# untitled.net
KiCad netlist of a schematic drawn in EAGLE
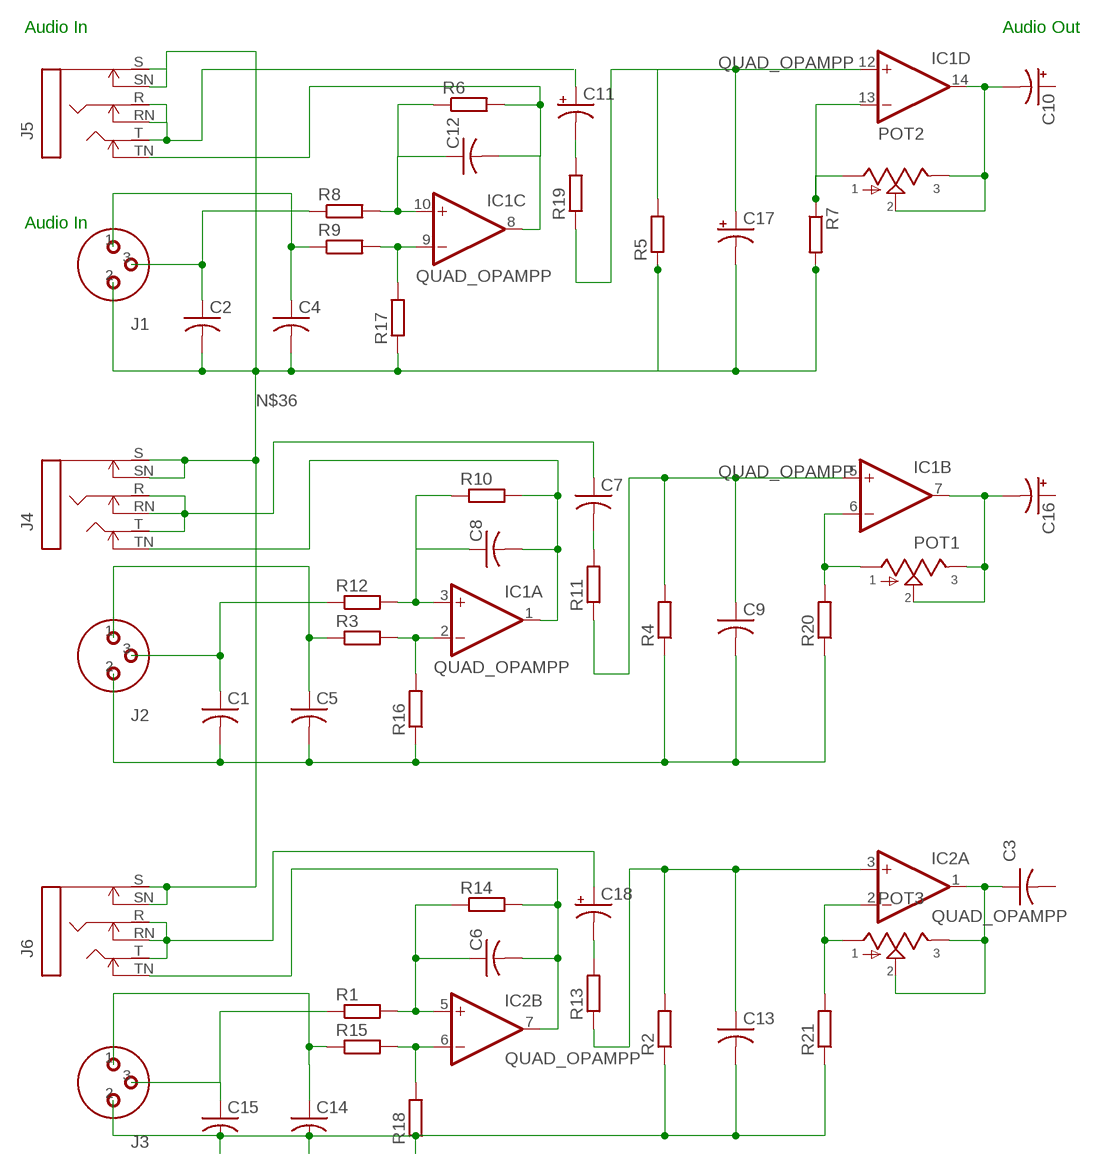
[diagram p0: schematic, sheet 1]

(export (version "E")
  (design (tool "Eeschema 10.0.6"))
  (components
    (comp (ref "C1")
      (value "C-US025-030X050")
      (footprint "eagle-import:C025-030X050")
      (libsource (lib "eagle-import") (part "C-US025-030X050"))
    )
    (comp (ref "C2")
      (value "C-US025-030X050")
      (footprint "eagle-import:C025-030X050")
      (libsource (lib "eagle-import") (part "C-US025-030X050"))
    )
    (comp (ref "C3")
      (value "C-US025-030X050")
      (footprint "eagle-import:C025-030X050")
      (libsource (lib "eagle-import") (part "C-US025-030X050"))
    )
    (comp (ref "C4")
      (value "C-US025-030X050")
      (footprint "eagle-import:C025-030X050")
      (libsource (lib "eagle-import") (part "C-US025-030X050"))
    )
    (comp (ref "C5")
      (value "C-US025-030X050")
      (footprint "eagle-import:C025-030X050")
      (libsource (lib "eagle-import") (part "C-US025-030X050"))
    )
    (comp (ref "C6")
      (value "C-US025-030X050")
      (footprint "eagle-import:C025-030X050")
      (libsource (lib "eagle-import") (part "C-US025-030X050"))
    )
    (comp (ref "C7")
      (value "C-US025-030X050")
      (footprint "eagle-import:C025-030X050")
      (libsource (lib "eagle-import") (part "C-US025-030X050"))
    )
    (comp (ref "C8")
      (value "C-US025-030X050")
      (footprint "eagle-import:C025-030X050")
      (libsource (lib "eagle-import") (part "C-US025-030X050"))
    )
    (comp (ref "C9")
      (value "C-US025-030X050")
      (footprint "eagle-import:C025-030X050")
      (libsource (lib "eagle-import") (part "C-US025-030X050"))
    )
    (comp (ref "C10")
      (value "CPOL-USE1.8-4")
      (footprint "eagle-import:E1,8-4")
      (libsource (lib "eagle-import") (part "CPOL-USE1.8-4"))
    )
    (comp (ref "C11")
      (value "CPOL-USE1.8-4")
      (footprint "eagle-import:E1,8-4")
      (libsource (lib "eagle-import") (part "CPOL-USE1.8-4"))
    )
    (comp (ref "C12")
      (value "C-US025-030X050")
      (footprint "eagle-import:C025-030X050")
      (libsource (lib "eagle-import") (part "C-US025-030X050"))
    )
    (comp (ref "C13")
      (value "C-US025-030X050")
      (footprint "eagle-import:C025-030X050")
      (libsource (lib "eagle-import") (part "C-US025-030X050"))
    )
    (comp (ref "C14")
      (value "C-US025-030X050")
      (footprint "eagle-import:C025-030X050")
      (libsource (lib "eagle-import") (part "C-US025-030X050"))
    )
    (comp (ref "C15")
      (value "C-US025-030X050")
      (footprint "eagle-import:C025-030X050")
      (libsource (lib "eagle-import") (part "C-US025-030X050"))
    )
    (comp (ref "C16")
      (value "CPOL-USE1.8-4")
      (footprint "eagle-import:E1,8-4")
      (libsource (lib "eagle-import") (part "CPOL-USE1.8-4"))
    )
    (comp (ref "C17")
      (value "CPOL-USE1.8-4")
      (footprint "eagle-import:E1,8-4")
      (libsource (lib "eagle-import") (part "CPOL-USE1.8-4"))
    )
    (comp (ref "C18")
      (value "CPOL-USE1.8-4")
      (footprint "eagle-import:E1,8-4")
      (libsource (lib "eagle-import") (part "CPOL-USE1.8-4"))
    )
    (comp (ref "IC1")
      (value "QUAD_OPAMPP")
      (footprint "eagle-import:DIL14")
      (libsource (lib "eagle-import") (part "QUAD_OPAMPP"))
    )
    (comp (ref "IC2")
      (value "QUAD_OPAMPP")
      (footprint "eagle-import:DIL14")
      (libsource (lib "eagle-import") (part "QUAD_OPAMPP"))
    )
    (comp (ref "J1")
      (value "XLR")
      (footprint "eagle-import:XLR_PADS")
      (libsource (lib "eagle-import") (part "XLR"))
    )
    (comp (ref "J2")
      (value "XLR")
      (footprint "eagle-import:XLR_PADS")
      (libsource (lib "eagle-import") (part "XLR"))
    )
    (comp (ref "J3")
      (value "XLR")
      (footprint "eagle-import:XLR_PADS")
      (libsource (lib "eagle-import") (part "XLR"))
    )
    (comp (ref "J4")
      (value "STEREOSWS")
      (footprint "eagle-import:NMJ6HC-S")
      (libsource (lib "eagle-import") (part "STEREOSWS"))
    )
    (comp (ref "J5")
      (value "STEREOSWS")
      (footprint "eagle-import:NMJ6HC-S")
      (libsource (lib "eagle-import") (part "STEREOSWS"))
    )
    (comp (ref "J6")
      (value "STEREOSWS")
      (footprint "eagle-import:NMJ6HC-S")
      (libsource (lib "eagle-import") (part "STEREOSWS"))
    )
    (comp (ref "POT1")
      (value "POT")
      (footprint "eagle-import:POT")
      (libsource (lib "eagle-import") (part "POT"))
    )
    (comp (ref "POT2")
      (value "POT")
      (footprint "eagle-import:POT")
      (libsource (lib "eagle-import") (part "POT"))
    )
    (comp (ref "POT3")
      (value "POT")
      (footprint "eagle-import:POT")
      (libsource (lib "eagle-import") (part "POT"))
    )
    (comp (ref "R1")
      (value "R-EU_0204/7")
      (footprint "eagle-import:0204_7")
      (libsource (lib "eagle-import") (part "R-EU_0204/7"))
    )
    (comp (ref "R2")
      (value "R-EU_0204/7")
      (footprint "eagle-import:0204_7")
      (libsource (lib "eagle-import") (part "R-EU_0204/7"))
    )
    (comp (ref "R3")
      (value "R-EU_0204/7")
      (footprint "eagle-import:0204_7")
      (libsource (lib "eagle-import") (part "R-EU_0204/7"))
    )
    (comp (ref "R4")
      (value "R-EU_0204/7")
      (footprint "eagle-import:0204_7")
      (libsource (lib "eagle-import") (part "R-EU_0204/7"))
    )
    (comp (ref "R5")
      (value "R-EU_0204/7")
      (footprint "eagle-import:0204_7")
      (libsource (lib "eagle-import") (part "R-EU_0204/7"))
    )
    (comp (ref "R6")
      (value "R-EU_0204/7")
      (footprint "eagle-import:0204_7")
      (libsource (lib "eagle-import") (part "R-EU_0204/7"))
    )
    (comp (ref "R7")
      (value "R-EU_0204/7")
      (footprint "eagle-import:0204_7")
      (libsource (lib "eagle-import") (part "R-EU_0204/7"))
    )
    (comp (ref "R8")
      (value "R-EU_0204/7")
      (footprint "eagle-import:0204_7")
      (libsource (lib "eagle-import") (part "R-EU_0204/7"))
    )
    (comp (ref "R9")
      (value "R-EU_0204/7")
      (footprint "eagle-import:0204_7")
      (libsource (lib "eagle-import") (part "R-EU_0204/7"))
    )
    (comp (ref "R10")
      (value "R-EU_0204/7")
      (footprint "eagle-import:0204_7")
      (libsource (lib "eagle-import") (part "R-EU_0204/7"))
    )
    (comp (ref "R11")
      (value "R-EU_0204/7")
      (footprint "eagle-import:0204_7")
      (libsource (lib "eagle-import") (part "R-EU_0204/7"))
    )
    (comp (ref "R12")
      (value "R-EU_0204/7")
      (footprint "eagle-import:0204_7")
      (libsource (lib "eagle-import") (part "R-EU_0204/7"))
    )
    (comp (ref "R13")
      (value "R-EU_0204/7")
      (footprint "eagle-import:0204_7")
      (libsource (lib "eagle-import") (part "R-EU_0204/7"))
    )
    (comp (ref "R14")
      (value "R-EU_0204/7")
      (footprint "eagle-import:0204_7")
      (libsource (lib "eagle-import") (part "R-EU_0204/7"))
    )
    (comp (ref "R15")
      (value "R-EU_0204/7")
      (footprint "eagle-import:0204_7")
      (libsource (lib "eagle-import") (part "R-EU_0204/7"))
    )
    (comp (ref "R16")
      (value "R-EU_0204/7")
      (footprint "eagle-import:0204_7")
      (libsource (lib "eagle-import") (part "R-EU_0204/7"))
    )
    (comp (ref "R17")
      (value "R-EU_0204/7")
      (footprint "eagle-import:0204_7")
      (libsource (lib "eagle-import") (part "R-EU_0204/7"))
    )
    (comp (ref "R18")
      (value "R-EU_0204/7")
      (footprint "eagle-import:0204_7")
      (libsource (lib "eagle-import") (part "R-EU_0204/7"))
    )
    (comp (ref "R19")
      (value "R-EU_0204/7")
      (footprint "eagle-import:0204_7")
      (libsource (lib "eagle-import") (part "R-EU_0204/7"))
    )
    (comp (ref "R20")
      (value "R-EU_0204/7")
      (footprint "eagle-import:0204_7")
      (libsource (lib "eagle-import") (part "R-EU_0204/7"))
    )
    (comp (ref "R21")
      (value "R-EU_0204/7")
      (footprint "eagle-import:0204_7")
      (libsource (lib "eagle-import") (part "R-EU_0204/7"))
    )
  )
  (nets
    (net (code "1") (name "/N$36") (class "Default")
      (node (ref "C17") (pin "-") (pinfunction "-_-") (pintype "passive"))
      (node (ref "C2") (pin "2") (pinfunction "2_2") (pintype "passive"))
      (node (ref "C4") (pin "2") (pinfunction "2_2") (pintype "passive"))
      (node (ref "J1") (pin "2") (pinfunction "2_2") (pintype "passive"))
      (node (ref "J4") (pin "S") (pinfunction "S_S") (pintype "passive"))
      (node (ref "J4") (pin "SN") (pinfunction "SN_SN") (pintype "passive"))
      (node (ref "J5") (pin "S") (pinfunction "S_S") (pintype "passive"))
      (node (ref "J5") (pin "SN") (pinfunction "SN_SN") (pintype "passive"))
      (node (ref "J6") (pin "S") (pinfunction "S_S") (pintype "passive"))
      (node (ref "J6") (pin "SN") (pinfunction "SN_SN") (pintype "passive"))
      (node (ref "R17") (pin "1") (pinfunction "1_1") (pintype "passive"))
      (node (ref "R5") (pin "1") (pinfunction "1_1") (pintype "passive"))
      (node (ref "R7") (pin "2") (pinfunction "2_2") (pintype "passive"))
    )
    (net (code "2") (name "Net-(C1-Pad1)") (class "Default")
      (node (ref "C1") (pin "1") (pinfunction "1_1") (pintype "passive"))
      (node (ref "J2") (pin "3") (pinfunction "3_3") (pintype "passive"))
      (node (ref "R12") (pin "1") (pinfunction "1_1") (pintype "passive"))
    )
    (net (code "3") (name "Net-(C1-Pad2)") (class "Default")
      (node (ref "C1") (pin "2") (pinfunction "2_2") (pintype "passive"))
      (node (ref "C5") (pin "2") (pinfunction "2_2") (pintype "passive"))
      (node (ref "C9") (pin "2") (pinfunction "2_2") (pintype "passive"))
      (node (ref "J2") (pin "2") (pinfunction "2_2") (pintype "passive"))
      (node (ref "R16") (pin "1") (pinfunction "1_1") (pintype "passive"))
      (node (ref "R20") (pin "1") (pinfunction "1_1") (pintype "passive"))
      (node (ref "R4") (pin "1") (pinfunction "1_1") (pintype "passive"))
    )
    (net (code "4") (name "Net-(C2-Pad1)") (class "Default")
      (node (ref "C2") (pin "1") (pinfunction "1_1") (pintype "passive"))
      (node (ref "J1") (pin "3") (pinfunction "3_3") (pintype "passive"))
      (node (ref "R8") (pin "1") (pinfunction "1_1") (pintype "passive"))
    )
    (net (code "5") (name "Net-(C4-Pad1)") (class "Default")
      (node (ref "C4") (pin "1") (pinfunction "1_1") (pintype "passive"))
      (node (ref "J1") (pin "1") (pinfunction "1_1") (pintype "passive"))
      (node (ref "R9") (pin "1") (pinfunction "1_1") (pintype "passive"))
    )
    (net (code "6") (name "Net-(C5-Pad1)") (class "Default")
      (node (ref "C5") (pin "1") (pinfunction "1_1") (pintype "passive"))
      (node (ref "J2") (pin "1") (pinfunction "1_1") (pintype "passive"))
      (node (ref "R3") (pin "1") (pinfunction "1_1") (pintype "passive"))
    )
    (net (code "7") (name "Net-(C7-Pad1)") (class "Default")
      (node (ref "C7") (pin "1") (pinfunction "1_1") (pintype "passive"))
      (node (ref "J4") (pin "R") (pinfunction "R_R") (pintype "passive"))
      (node (ref "J4") (pin "RN") (pinfunction "RN_RN") (pintype "passive"))
      (node (ref "J4") (pin "T") (pinfunction "T_T") (pintype "passive"))
    )
    (net (code "8") (name "Net-(C7-Pad2)") (class "Default")
      (node (ref "C7") (pin "2") (pinfunction "2_2") (pintype "passive"))
      (node (ref "R11") (pin "2") (pinfunction "2_2") (pintype "passive"))
    )
    (net (code "9") (name "Net-(C11-Pad-)") (class "Default")
      (node (ref "C11") (pin "-") (pinfunction "-_-") (pintype "passive"))
      (node (ref "R19") (pin "2") (pinfunction "2_2") (pintype "passive"))
    )
    (net (code "10") (name "Net-(C13-Pad2)") (class "Default")
      (node (ref "C13") (pin "2") (pinfunction "2_2") (pintype "passive"))
      (node (ref "C14") (pin "2") (pinfunction "2_2") (pintype "passive"))
      (node (ref "C15") (pin "2") (pinfunction "2_2") (pintype "passive"))
      (node (ref "J3") (pin "2") (pinfunction "2_2") (pintype "passive"))
      (node (ref "R18") (pin "1") (pinfunction "1_1") (pintype "passive"))
      (node (ref "R2") (pin "1") (pinfunction "1_1") (pintype "passive"))
      (node (ref "R21") (pin "1") (pinfunction "1_1") (pintype "passive"))
    )
    (net (code "11") (name "Net-(C14-Pad1)") (class "Default")
      (node (ref "C14") (pin "1") (pinfunction "1_1") (pintype "passive"))
      (node (ref "J3") (pin "1") (pinfunction "1_1") (pintype "passive"))
      (node (ref "R15") (pin "1") (pinfunction "1_1") (pintype "passive"))
    )
    (net (code "12") (name "Net-(C15-Pad1)") (class "Default")
      (node (ref "C15") (pin "1") (pinfunction "1_1") (pintype "passive"))
      (node (ref "J3") (pin "3") (pinfunction "3_3") (pintype "passive"))
      (node (ref "R1") (pin "1") (pinfunction "1_1") (pintype "passive"))
    )
    (net (code "13") (name "Net-(C18-Pad+)") (class "Default")
      (node (ref "C18") (pin "+") (pinfunction "+_+") (pintype "passive"))
      (node (ref "J6") (pin "R") (pinfunction "R_R") (pintype "passive"))
      (node (ref "J6") (pin "RN") (pinfunction "RN_RN") (pintype "passive"))
      (node (ref "J6") (pin "T") (pinfunction "T_T") (pintype "passive"))
    )
    (net (code "14") (name "Net-(C18-Pad-)") (class "Default")
      (node (ref "C18") (pin "-") (pinfunction "-_-") (pintype "passive"))
      (node (ref "R13") (pin "2") (pinfunction "2_2") (pintype "passive"))
    )
    (net (code "15") (name "Net-(IC1A-+IN)") (class "Default")
      (node (ref "C8") (pin "1") (pinfunction "1_1") (pintype "passive"))
      (node (ref "IC1") (pin "3") (pinfunction "+IN_3") (pintype "input"))
      (node (ref "R10") (pin "1") (pinfunction "1_1") (pintype "passive"))
      (node (ref "R12") (pin "2") (pinfunction "2_2") (pintype "passive"))
    )
    (net (code "16") (name "Net-(IC1A--IN)") (class "Default")
      (node (ref "IC1") (pin "2") (pinfunction "-IN_2") (pintype "input"))
      (node (ref "R16") (pin "2") (pinfunction "2_2") (pintype "passive"))
      (node (ref "R3") (pin "2") (pinfunction "2_2") (pintype "passive"))
    )
    (net (code "17") (name "Net-(IC1A-OUT)") (class "Default")
      (node (ref "C8") (pin "2") (pinfunction "2_2") (pintype "passive"))
      (node (ref "IC1") (pin "1") (pinfunction "OUT_1") (pintype "output"))
      (node (ref "J4") (pin "TN") (pinfunction "TN_TN") (pintype "passive"))
      (node (ref "R10") (pin "2") (pinfunction "2_2") (pintype "passive"))
    )
    (net (code "18") (name "Net-(IC1B-+IN)") (class "Default")
      (node (ref "C9") (pin "1") (pinfunction "1_1") (pintype "passive"))
      (node (ref "IC1") (pin "5") (pinfunction "+IN_5") (pintype "input"))
      (node (ref "R11") (pin "1") (pinfunction "1_1") (pintype "passive"))
      (node (ref "R4") (pin "2") (pinfunction "2_2") (pintype "passive"))
    )
    (net (code "19") (name "Net-(IC1B--IN)") (class "Default")
      (node (ref "IC1") (pin "6") (pinfunction "-IN_6") (pintype "input"))
      (node (ref "POT1") (pin "1") (pinfunction "1_1") (pintype "passive"))
      (node (ref "R20") (pin "2") (pinfunction "2_2") (pintype "passive"))
    )
    (net (code "20") (name "Net-(IC1B-OUT)") (class "Default")
      (node (ref "C16") (pin "-") (pinfunction "-_-") (pintype "passive"))
      (node (ref "IC1") (pin "7") (pinfunction "OUT_7") (pintype "output"))
      (node (ref "POT1") (pin "2") (pinfunction "2_2") (pintype "passive"))
      (node (ref "POT1") (pin "3") (pinfunction "3_3") (pintype "passive"))
    )
    (net (code "21") (name "Net-(IC1C-+IN)") (class "Default")
      (node (ref "C12") (pin "1") (pinfunction "1_1") (pintype "passive"))
      (node (ref "IC1") (pin "10") (pinfunction "+IN_10") (pintype "input"))
      (node (ref "R6") (pin "1") (pinfunction "1_1") (pintype "passive"))
      (node (ref "R8") (pin "2") (pinfunction "2_2") (pintype "passive"))
    )
    (net (code "22") (name "Net-(IC1C--IN)") (class "Default")
      (node (ref "IC1") (pin "9") (pinfunction "-IN_9") (pintype "input"))
      (node (ref "R17") (pin "2") (pinfunction "2_2") (pintype "passive"))
      (node (ref "R9") (pin "2") (pinfunction "2_2") (pintype "passive"))
    )
    (net (code "23") (name "Net-(IC1C-OUT)") (class "Default")
      (node (ref "C12") (pin "2") (pinfunction "2_2") (pintype "passive"))
      (node (ref "IC1") (pin "8") (pinfunction "OUT_8") (pintype "output"))
      (node (ref "J5") (pin "TN") (pinfunction "TN_TN") (pintype "passive"))
      (node (ref "R6") (pin "2") (pinfunction "2_2") (pintype "passive"))
    )
    (net (code "24") (name "Net-(IC1D-+IN)") (class "Default")
      (node (ref "C17") (pin "+") (pinfunction "+_+") (pintype "passive"))
      (node (ref "IC1") (pin "12") (pinfunction "+IN_12") (pintype "input"))
      (node (ref "R19") (pin "1") (pinfunction "1_1") (pintype "passive"))
      (node (ref "R5") (pin "2") (pinfunction "2_2") (pintype "passive"))
    )
    (net (code "25") (name "Net-(IC1D--IN)") (class "Default")
      (node (ref "IC1") (pin "13") (pinfunction "-IN_13") (pintype "input"))
      (node (ref "POT2") (pin "1") (pinfunction "1_1") (pintype "passive"))
      (node (ref "R7") (pin "1") (pinfunction "1_1") (pintype "passive"))
    )
    (net (code "26") (name "Net-(IC1D-OUT)") (class "Default")
      (node (ref "C10") (pin "-") (pinfunction "-_-") (pintype "passive"))
      (node (ref "IC1") (pin "14") (pinfunction "OUT_14") (pintype "output"))
      (node (ref "POT2") (pin "2") (pinfunction "2_2") (pintype "passive"))
      (node (ref "POT2") (pin "3") (pinfunction "3_3") (pintype "passive"))
    )
    (net (code "27") (name "Net-(IC2A-+IN)") (class "Default")
      (node (ref "C13") (pin "1") (pinfunction "1_1") (pintype "passive"))
      (node (ref "IC2") (pin "3") (pinfunction "+IN_3") (pintype "input"))
      (node (ref "R13") (pin "1") (pinfunction "1_1") (pintype "passive"))
      (node (ref "R2") (pin "2") (pinfunction "2_2") (pintype "passive"))
    )
    (net (code "28") (name "Net-(IC2A--IN)") (class "Default")
      (node (ref "IC2") (pin "2") (pinfunction "-IN_2") (pintype "input"))
      (node (ref "POT3") (pin "1") (pinfunction "1_1") (pintype "passive"))
      (node (ref "R21") (pin "2") (pinfunction "2_2") (pintype "passive"))
    )
    (net (code "29") (name "Net-(IC2A-OUT)") (class "Default")
      (node (ref "C3") (pin "1") (pinfunction "1_1") (pintype "passive"))
      (node (ref "IC2") (pin "1") (pinfunction "OUT_1") (pintype "output"))
      (node (ref "POT3") (pin "2") (pinfunction "2_2") (pintype "passive"))
      (node (ref "POT3") (pin "3") (pinfunction "3_3") (pintype "passive"))
    )
    (net (code "30") (name "Net-(IC2B-+IN)") (class "Default")
      (node (ref "C6") (pin "1") (pinfunction "1_1") (pintype "passive"))
      (node (ref "IC2") (pin "5") (pinfunction "+IN_5") (pintype "input"))
      (node (ref "R1") (pin "2") (pinfunction "2_2") (pintype "passive"))
      (node (ref "R14") (pin "1") (pinfunction "1_1") (pintype "passive"))
    )
    (net (code "31") (name "Net-(IC2B--IN)") (class "Default")
      (node (ref "IC2") (pin "6") (pinfunction "-IN_6") (pintype "input"))
      (node (ref "R15") (pin "2") (pinfunction "2_2") (pintype "passive"))
      (node (ref "R18") (pin "2") (pinfunction "2_2") (pintype "passive"))
    )
    (net (code "32") (name "Net-(IC2B-OUT)") (class "Default")
      (node (ref "C6") (pin "2") (pinfunction "2_2") (pintype "passive"))
      (node (ref "IC2") (pin "7") (pinfunction "OUT_7") (pintype "output"))
      (node (ref "J6") (pin "TN") (pinfunction "TN_TN") (pintype "passive"))
      (node (ref "R14") (pin "2") (pinfunction "2_2") (pintype "passive"))
    )
    (net (code "33") (name "Net-(J5-PadR)") (class "Default")
      (node (ref "J5") (pin "R") (pinfunction "R_R") (pintype "passive"))
      (node (ref "J5") (pin "RN") (pinfunction "RN_RN") (pintype "passive"))
      (node (ref "J5") (pin "T") (pinfunction "T_T") (pintype "passive"))
    )
    (net (code "34") (name "unconnected-(C3-Pad2)") (class "Default")
      (node (ref "C3") (pin "2") (pinfunction "2_2") (pintype "passive"))
    )
    (net (code "35") (name "unconnected-(C10-Pad+)") (class "Default")
      (node (ref "C10") (pin "+") (pinfunction "+_+") (pintype "passive"))
    )
    (net (code "36") (name "unconnected-(C11-Pad+)") (class "Default")
      (node (ref "C11") (pin "+") (pinfunction "+_+") (pintype "passive"))
    )
    (net (code "37") (name "unconnected-(C16-Pad+)") (class "Default")
      (node (ref "C16") (pin "+") (pinfunction "+_+") (pintype "passive"))
    )
  )
)
